# Carte_EV_2018.net
KiCad netlist of a schematic drawn in Altium Designer
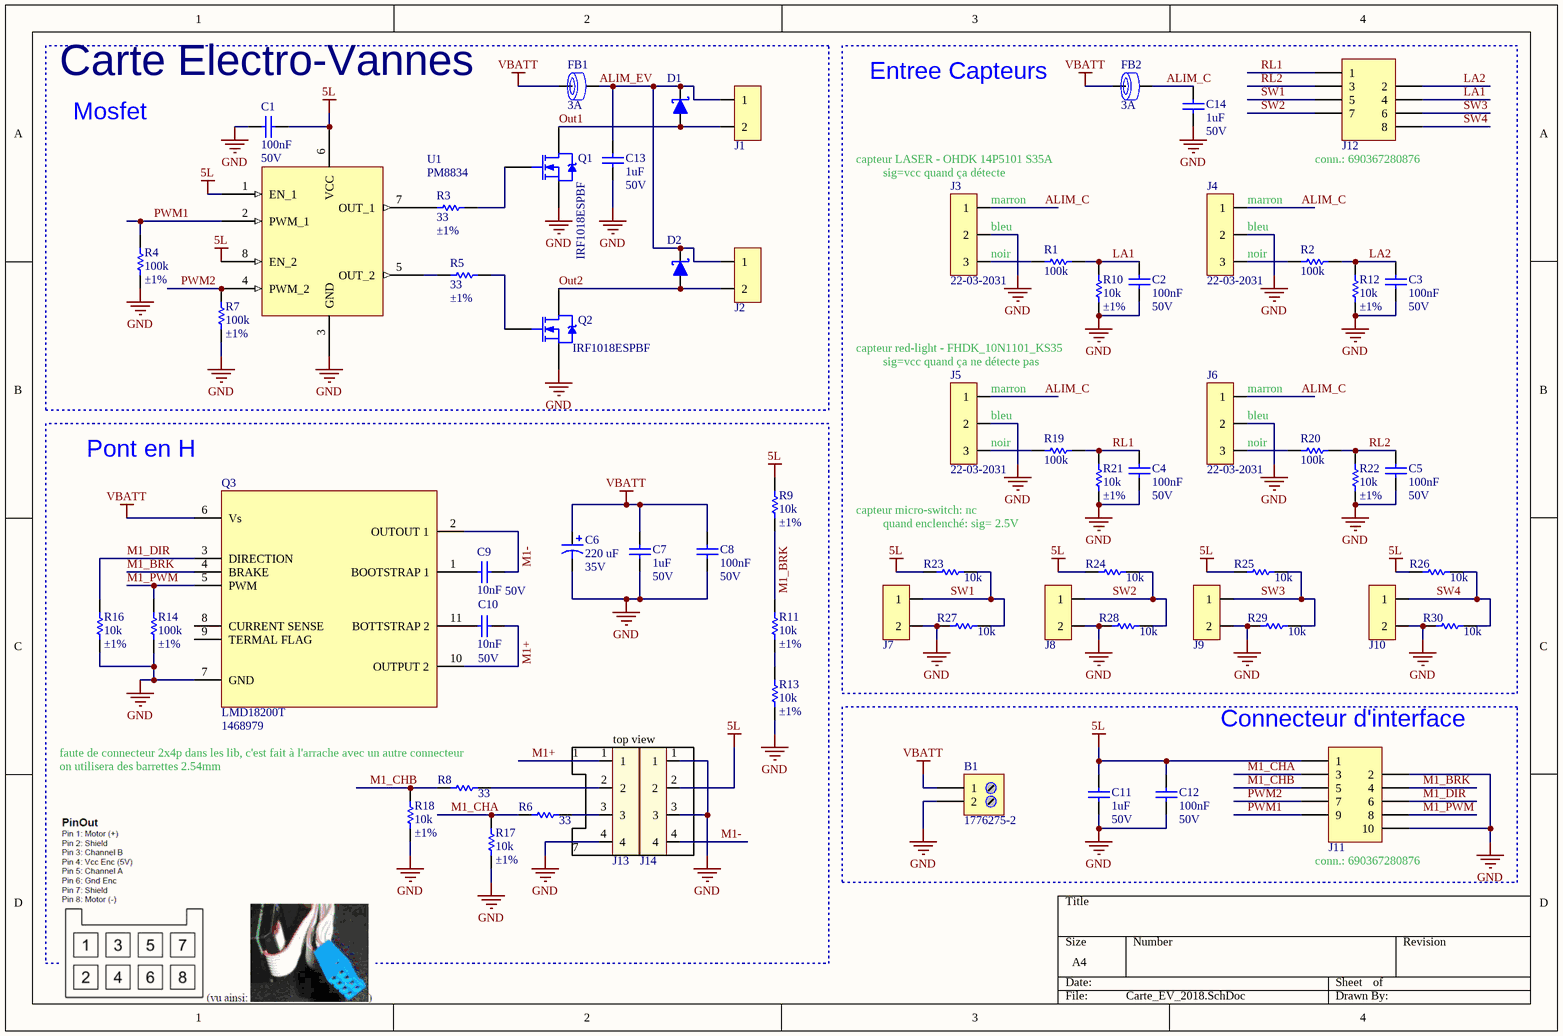
[diagram p0: Carte_EV_2018.SchDoc]

(export (version "E")
  (design (tool "Eeschema 10.0.6"))
  (components
    (comp (ref "B1")
      (value "1776275-2")
      (footprint "BORNIER_2V_3.5MM")
      (description "TERM BLOCK 2POS SIDE ENT 3.5MM")
      (fields (field (name "MANUFACTURER") "TE Connectivity AMP Connectors"))
      (libsource (lib "Divers") (part "1776275-2"))
    )
    (comp (ref "C1")
      (value "100nF")
      (footprint "WCAP-CSGP_0603, 1.6x0.8x0.8")
      (description "CAP CER 100nF 50V X7R 0603")
      (fields
        (field (name "MANUFACTURER") "Wurth Elektronik")
        (field (name "MANUFACTURER PART NUMBER") "885012206095")
        (field (name "RATEDVOLTAGE") "50V")
      )
      (libsource (lib "Condensateur") (part "WCAP-CSGP, 885012206095"))
    )
    (comp (ref "C2")
      (value "100nF")
      (footprint "WCAP-CSGP_0603, 1.6x0.8x0.8")
      (description "CAP CER 100nF 50V X7R 0603")
      (fields
        (field (name "MANUFACTURER") "Wurth Elektronik")
        (field (name "MANUFACTURER PART NUMBER") "885012206095")
        (field (name "RATEDVOLTAGE") "50V")
      )
      (libsource (lib "Condensateur") (part "WCAP-CSGP, 885012206095"))
    )
    (comp (ref "C3")
      (value "100nF")
      (footprint "WCAP-CSGP_0603, 1.6x0.8x0.8")
      (description "CAP CER 100nF 50V X7R 0603")
      (fields
        (field (name "MANUFACTURER") "Wurth Elektronik")
        (field (name "MANUFACTURER PART NUMBER") "885012206095")
        (field (name "RATEDVOLTAGE") "50V")
      )
      (libsource (lib "Condensateur") (part "WCAP-CSGP, 885012206095"))
    )
    (comp (ref "C4")
      (value "100nF")
      (footprint "WCAP-CSGP_0603, 1.6x0.8x0.8")
      (description "CAP CER 100nF 50V X7R 0603")
      (fields
        (field (name "MANUFACTURER") "Wurth Elektronik")
        (field (name "MANUFACTURER PART NUMBER") "885012206095")
        (field (name "RATEDVOLTAGE") "50V")
      )
      (libsource (lib "Condensateur") (part "WCAP-CSGP, 885012206095"))
    )
    (comp (ref "C5")
      (value "100nF")
      (footprint "WCAP-CSGP_0603, 1.6x0.8x0.8")
      (description "CAP CER 100nF 50V X7R 0603")
      (fields
        (field (name "MANUFACTURER") "Wurth Elektronik")
        (field (name "MANUFACTURER PART NUMBER") "885012206095")
        (field (name "RATEDVOLTAGE") "50V")
      )
      (libsource (lib "Condensateur") (part "WCAP-CSGP, 885012206095"))
    )
    (comp (ref "C6")
      (value "220 uF")
      (footprint "WCAP-ATG8_8x11.5x3.5x0.5")
      (description "CAP Alu 220 UF 20% 35 V")
      (fields
        (field (name "MANUFACTURER") "Wurth Elektronik")
        (field (name "MANUFACTURER PART NUMBER") "860010574011")
        (field (name "RATEDVOLTAGE") "35V")
      )
      (libsource (lib "Condensateur") (part "WCAP-ATG8, 860010574011"))
    )
    (comp (ref "C7")
      (value "1uF")
      (footprint "WCAP-CSGP_0805, 2x1.25x1.25")
      (description "CAP CER 1uF 50V X7R 0805")
      (fields
        (field (name "MANUFACTURER") "Wurth Elektronik")
        (field (name "MANUFACTURER PART NUMBER") "885012207103")
        (field (name "RATEDVOLTAGE") "50V")
      )
      (libsource (lib "Condensateur") (part "WCAP-CSGP, 885012207103"))
    )
    (comp (ref "C8")
      (value "100nF")
      (footprint "WCAP-CSGP_0603, 1.6x0.8x0.8")
      (description "CAP CER 100nF 50V X7R 0603")
      (fields
        (field (name "MANUFACTURER") "Wurth Elektronik")
        (field (name "MANUFACTURER PART NUMBER") "885012206095")
        (field (name "RATEDVOLTAGE") "50V")
      )
      (libsource (lib "Condensateur") (part "WCAP-CSGP, 885012206095"))
    )
    (comp (ref "C9")
      (value "10nF")
      (footprint "WCAP-CSGP_0603, 1.6x0.8x0.8")
      (description "CAP CER 10nF 50V X7R 0603")
      (fields
        (field (name "MANUFACTURER") "Wurth Elektronik")
        (field (name "MANUFACTURER PART NUMBER") "885012206089")
        (field (name "RATEDVOLTAGE") "50V")
      )
      (libsource (lib "Condensateur") (part "WCAP-CSGP, 885012206089"))
    )
    (comp (ref "C10")
      (value "10nF")
      (footprint "WCAP-CSGP_0603, 1.6x0.8x0.8")
      (description "CAP CER 10nF 50V X7R 0603")
      (fields
        (field (name "MANUFACTURER") "Wurth Elektronik")
        (field (name "MANUFACTURER PART NUMBER") "885012206089")
        (field (name "RATEDVOLTAGE") "50V")
      )
      (libsource (lib "Condensateur") (part "WCAP-CSGP, 885012206089"))
    )
    (comp (ref "C11")
      (value "1uF")
      (footprint "WCAP-CSGP_0805, 2x1.25x1.25")
      (description "CAP CER 1uF 50V X7R 0805")
      (fields
        (field (name "MANUFACTURER") "Wurth Elektronik")
        (field (name "MANUFACTURER PART NUMBER") "885012207103")
        (field (name "RATEDVOLTAGE") "50V")
      )
      (libsource (lib "Condensateur") (part "WCAP-CSGP, 885012207103"))
    )
    (comp (ref "C12")
      (value "100nF")
      (footprint "WCAP-CSGP_0603, 1.6x0.8x0.8")
      (description "CAP CER 100nF 50V X7R 0603")
      (fields
        (field (name "MANUFACTURER") "Wurth Elektronik")
        (field (name "MANUFACTURER PART NUMBER") "885012206095")
        (field (name "RATEDVOLTAGE") "50V")
      )
      (libsource (lib "Condensateur") (part "WCAP-CSGP, 885012206095"))
    )
    (comp (ref "C13")
      (value "1uF")
      (footprint "WCAP-CSGP_0805, 2x1.25x1.25")
      (description "CAP CER 1uF 50V X7R 0805")
      (fields
        (field (name "MANUFACTURER") "Wurth Elektronik")
        (field (name "MANUFACTURER PART NUMBER") "885012207103")
        (field (name "RATEDVOLTAGE") "50V")
      )
      (libsource (lib "Condensateur") (part "WCAP-CSGP, 885012207103"))
    )
    (comp (ref "C14")
      (value "1uF")
      (footprint "WCAP-CSGP_0805, 2x1.25x1.25")
      (description "CAP CER 1uF 50V X7R 0805")
      (fields
        (field (name "MANUFACTURER") "Wurth Elektronik")
        (field (name "MANUFACTURER PART NUMBER") "885012207103")
        (field (name "RATEDVOLTAGE") "50V")
      )
      (libsource (lib "Condensateur") (part "WCAP-CSGP, 885012207103"))
    )
    (comp (ref "D1")
      (value "RBR3MM40ATFTR")
      (footprint "Diode:SOD-123FL")
      (description "DIODE SCHOTTKY 40V 3A SOD123-FL")
      (fields (field (name "MANUFACTURER") "ROHM"))
      (libsource (lib "Diode") (part "RBR3MM40ATFTR"))
    )
    (comp (ref "D2")
      (value "RBR3MM40ATFTR")
      (footprint "Diode:SOD-123FL")
      (description "DIODE SCHOTTKY 40V 3A SOD123-FL")
      (fields (field (name "MANUFACTURER") "ROHM"))
      (libsource (lib "Diode") (part "RBR3MM40ATFTR"))
    )
    (comp (ref "FB1")
      (value "742792023")
      (footprint "WE-CBF_0805_High Current")
      (description "Ferrite Bead 120ohm 0805 max3.0A")
      (fields (field (name "MANUFACTURER") "Wurth Elektronik") (field (name "RATEDCURRENT") "3A"))
      (libsource (lib "Inductance") (part "WE-CBF, 742792023"))
    )
    (comp (ref "FB2")
      (value "742792023")
      (footprint "WE-CBF_0805_High Current")
      (description "Ferrite Bead 120ohm 0805 max3.0A")
      (fields (field (name "MANUFACTURER") "Wurth Elektronik") (field (name "RATEDCURRENT") "3A"))
      (libsource (lib "Inductance") (part "WE-CBF, 742792023"))
    )
    (comp (ref "J1")
      (value "22-03-2021")
      (footprint "22-03-2021")
      (libsource (lib "Connecteurs") (part "22-03-2021"))
    )
    (comp (ref "J2")
      (value "22-03-2021")
      (footprint "22-03-2021")
      (libsource (lib "Connecteurs") (part "22-03-2021"))
    )
    (comp (ref "J3")
      (value "22-03-2031")
      (footprint "22-03-2031")
      (libsource (lib "Connecteurs") (part "22-03-2031"))
    )
    (comp (ref "J4")
      (value "22-03-2031")
      (footprint "22-03-2031")
      (libsource (lib "Connecteurs") (part "22-03-2031"))
    )
    (comp (ref "J5")
      (value "22-03-2031")
      (footprint "22-03-2031")
      (libsource (lib "Connecteurs") (part "22-03-2031"))
    )
    (comp (ref "J6")
      (value "22-03-2031")
      (footprint "22-03-2031")
      (libsource (lib "Connecteurs") (part "22-03-2031"))
    )
    (comp (ref "J7") (value "22-03-2021") (footprint "22-03-2021") (libsource (lib "") (part "22-03-2021_1")))
    (comp (ref "J8") (value "22-03-2021") (footprint "22-03-2021") (libsource (lib "") (part "22-03-2021_1")))
    (comp (ref "J9") (value "22-03-2021") (footprint "22-03-2021") (libsource (lib "") (part "22-03-2021_1")))
    (comp (ref "J10")
      (value "22-03-2021")
      (footprint "22-03-2021")
      (libsource (lib "") (part "22-03-2021_1"))
    )
    (comp (ref "J11")
      (value "690367281076")
      (footprint "690367281076")
      (description "WR-MM 10p Female SMT Connector with Polarization")
      (fields (field (name "MANUFACTURER") "Wurth Electronics Inc."))
      (libsource (lib "Connecteurs") (part "690367281076"))
    )
    (comp (ref "J12")
      (value "690367280876")
      (footprint "690367280876")
      (description "WR-MM 8p Female SMT Connector with Polarization")
      (fields (field (name "MANUFACTURER") "Wurth Electronics Inc."))
      (libsource (lib "Connecteurs") (part "690367280876"))
    )
    (comp (ref "J13")
      (value "22-27-2041")
      (footprint "22-27-2041")
      (fields (field (name "MANUFACTURER PART NUMBER") "22-27-2041.."))
      (libsource (lib "") (part "22-27-2041_1"))
    )
    (comp (ref "J14")
      (value "22-27-2041")
      (footprint "22-27-2041")
      (fields (field (name "MANUFACTURER PART NUMBER") "22-27-2041.."))
      (libsource (lib "Connecteurs") (part "22-27-2041"))
    )
    (comp (ref "Q1")
      (value "IRF1018ESPBF")
      (footprint "D2Pak / AAVID 7109DG")
      (description "MOSFET N-CH 60V 79A D2PAK")
      (fields (field (name "MANUFACTURER") "Infineon Technologies"))
      (libsource (lib "Transistors") (part "IRF1018ESPBF"))
    )
    (comp (ref "Q2")
      (value "IRF1018ESPBF")
      (footprint "D2Pak / AAVID 7109DG")
      (description "MOSFET N-CH 60V 79A D2PAK")
      (fields (field (name "MANUFACTURER") "Infineon Technologies"))
      (libsource (lib "Transistors") (part "IRF1018ESPBF"))
    )
    (comp (ref "Q3")
      (value "LMD18200T")
      (footprint "LMD18200T")
      (fields
        (field (name "MANUFACTURER PART NUMBER") "LMD18200T/NOPB")
        (field (name "MANUFACTURER") "TEXAS INSTRUMENTS")
        (field (name "SUPPLIER PART NUMBER 1") "1468979")
      )
      (libsource (lib "Transistors") (part "LMD18200T"))
    )
    (comp (ref "R1")
      (value "100k")
      (footprint "RESC1608X06N")
      (description "RES SMD 100K OHM 1% 1/10W 0603")
      (fields
        (field (name "MANUFACTURER") "Yageo")
        (field (name "MANUFACTURER PART NUMBER") "RC0603FR-07100KL")
      )
      (libsource (lib "Resistance") (part "RC0603FR-07100KL"))
    )
    (comp (ref "R2")
      (value "100k")
      (footprint "RESC1608X06N")
      (description "RES SMD 100K OHM 1% 1/10W 0603")
      (fields
        (field (name "MANUFACTURER") "Yageo")
        (field (name "MANUFACTURER PART NUMBER") "RC0603FR-07100KL")
      )
      (libsource (lib "Resistance") (part "RC0603FR-07100KL"))
    )
    (comp (ref "R3")
      (value "33")
      (footprint "RESC1608X06N")
      (description "RES SMD 33 OHM 1% 1/10W 0603")
      (fields
        (field (name "MANUFACTURER") "Yageo")
        (field (name "MANUFACTURER PART NUMBER") "RC0603FR-0733RL")
        (field (name "PRECISION") "±1%")
      )
      (libsource (lib "Resistance") (part "RC0603FR-0733RL"))
    )
    (comp (ref "R4")
      (value "100k")
      (footprint "RESC1608X06N")
      (description "RES SMD 100K OHM 1% 1/10W 0603")
      (fields
        (field (name "MANUFACTURER") "Yageo")
        (field (name "MANUFACTURER PART NUMBER") "RC0603FR-07100KL")
        (field (name "PRECISION") "±1%")
      )
      (libsource (lib "Resistance") (part "RC0603FR-07100KL"))
    )
    (comp (ref "R5")
      (value "33")
      (footprint "RESC1608X06N")
      (description "RES SMD 33 OHM 1% 1/10W 0603")
      (fields
        (field (name "MANUFACTURER") "Yageo")
        (field (name "MANUFACTURER PART NUMBER") "RC0603FR-0733RL")
        (field (name "PRECISION") "±1%")
      )
      (libsource (lib "Resistance") (part "RC0603FR-0733RL"))
    )
    (comp (ref "R6")
      (value "33")
      (footprint "RESC1608X06N")
      (description "RES SMD 33 OHM 1% 1/10W 0603")
      (fields
        (field (name "MANUFACTURER") "Yageo")
        (field (name "MANUFACTURER PART NUMBER") "RC0603FR-0733RL")
      )
      (libsource (lib "Resistance") (part "RC0603FR-0733RL"))
    )
    (comp (ref "R7")
      (value "100k")
      (footprint "RESC1608X06N")
      (description "RES SMD 100K OHM 1% 1/10W 0603")
      (fields
        (field (name "MANUFACTURER") "Yageo")
        (field (name "MANUFACTURER PART NUMBER") "RC0603FR-07100KL")
        (field (name "PRECISION") "±1%")
      )
      (libsource (lib "Resistance") (part "RC0603FR-07100KL"))
    )
    (comp (ref "R8")
      (value "33")
      (footprint "RESC1608X06N")
      (description "RES SMD 33 OHM 1% 1/10W 0603")
      (fields
        (field (name "MANUFACTURER") "Yageo")
        (field (name "MANUFACTURER PART NUMBER") "RC0603FR-0733RL")
      )
      (libsource (lib "Resistance") (part "RC0603FR-0733RL"))
    )
    (comp (ref "R9")
      (value "10k")
      (footprint "RESC1608X06N")
      (description "RES SMD 10K OHM 1% 1/10W 0603")
      (fields
        (field (name "MANUFACTURER") "Yageo")
        (field (name "MANUFACTURER PART NUMBER") "RC0603FR-0710KL")
        (field (name "PRECISION") "±1%")
      )
      (libsource (lib "Resistance") (part "RC0603FR-0710KL"))
    )
    (comp (ref "R10")
      (value "10k")
      (footprint "RESC1608X06N")
      (description "RES SMD 10K OHM 1% 1/10W 0603")
      (fields
        (field (name "MANUFACTURER") "Yageo")
        (field (name "MANUFACTURER PART NUMBER") "RC0603FR-0710KL")
        (field (name "PRECISION") "±1%")
      )
      (libsource (lib "Resistance") (part "RC0603FR-0710KL"))
    )
    (comp (ref "R11")
      (value "10k")
      (footprint "RESC1608X06N")
      (description "RES SMD 10K OHM 1% 1/10W 0603")
      (fields
        (field (name "MANUFACTURER") "Yageo")
        (field (name "MANUFACTURER PART NUMBER") "RC0603FR-0710KL")
        (field (name "PRECISION") "±1%")
      )
      (libsource (lib "Resistance") (part "RC0603FR-0710KL"))
    )
    (comp (ref "R12")
      (value "10k")
      (footprint "RESC1608X06N")
      (description "RES SMD 10K OHM 1% 1/10W 0603")
      (fields
        (field (name "MANUFACTURER") "Yageo")
        (field (name "MANUFACTURER PART NUMBER") "RC0603FR-0710KL")
        (field (name "PRECISION") "±1%")
      )
      (libsource (lib "Resistance") (part "RC0603FR-0710KL"))
    )
    (comp (ref "R13")
      (value "10k")
      (footprint "RESC1608X06N")
      (description "RES SMD 10K OHM 1% 1/10W 0603")
      (fields
        (field (name "MANUFACTURER") "Yageo")
        (field (name "MANUFACTURER PART NUMBER") "RC0603FR-0710KL")
        (field (name "PRECISION") "±1%")
      )
      (libsource (lib "Resistance") (part "RC0603FR-0710KL"))
    )
    (comp (ref "R14")
      (value "100k")
      (footprint "RESC1608X06N")
      (description "RES SMD 100K OHM 1% 1/10W 0603")
      (fields
        (field (name "MANUFACTURER") "Yageo")
        (field (name "MANUFACTURER PART NUMBER") "RC0603FR-07100KL")
        (field (name "PRECISION") "±1%")
      )
      (libsource (lib "Resistance") (part "RC0603FR-07100KL"))
    )
    (comp (ref "R16")
      (value "10k")
      (footprint "RESC1608X06N")
      (description "RES SMD 10K OHM 1% 1/10W 0603")
      (fields
        (field (name "MANUFACTURER") "Yageo")
        (field (name "MANUFACTURER PART NUMBER") "RC0603FR-0710KL")
        (field (name "PRECISION") "±1%")
      )
      (libsource (lib "Resistance") (part "RC0603FR-0710KL"))
    )
    (comp (ref "R17")
      (value "10k")
      (footprint "RESC1608X06N")
      (description "RES SMD 10K OHM 1% 1/10W 0603")
      (fields
        (field (name "MANUFACTURER") "Yageo")
        (field (name "MANUFACTURER PART NUMBER") "RC0603FR-0710KL")
        (field (name "PRECISION") "±1%")
      )
      (libsource (lib "Resistance") (part "RC0603FR-0710KL"))
    )
    (comp (ref "R18")
      (value "10k")
      (footprint "RESC1608X06N")
      (description "RES SMD 10K OHM 1% 1/10W 0603")
      (fields
        (field (name "MANUFACTURER") "Yageo")
        (field (name "MANUFACTURER PART NUMBER") "RC0603FR-0710KL")
        (field (name "PRECISION") "±1%")
      )
      (libsource (lib "Resistance") (part "RC0603FR-0710KL"))
    )
    (comp (ref "R19")
      (value "100k")
      (footprint "RESC1608X06N")
      (description "RES SMD 100K OHM 1% 1/10W 0603")
      (fields
        (field (name "MANUFACTURER") "Yageo")
        (field (name "MANUFACTURER PART NUMBER") "RC0603FR-07100KL")
      )
      (libsource (lib "Resistance") (part "RC0603FR-07100KL"))
    )
    (comp (ref "R20")
      (value "100k")
      (footprint "RESC1608X06N")
      (description "RES SMD 100K OHM 1% 1/10W 0603")
      (fields
        (field (name "MANUFACTURER") "Yageo")
        (field (name "MANUFACTURER PART NUMBER") "RC0603FR-07100KL")
      )
      (libsource (lib "Resistance") (part "RC0603FR-07100KL"))
    )
    (comp (ref "R21")
      (value "10k")
      (footprint "RESC1608X06N")
      (description "RES SMD 10K OHM 1% 1/10W 0603")
      (fields
        (field (name "MANUFACTURER") "Yageo")
        (field (name "MANUFACTURER PART NUMBER") "RC0603FR-0710KL")
        (field (name "PRECISION") "±1%")
      )
      (libsource (lib "Resistance") (part "RC0603FR-0710KL"))
    )
    (comp (ref "R22")
      (value "10k")
      (footprint "RESC1608X06N")
      (description "RES SMD 10K OHM 1% 1/10W 0603")
      (fields
        (field (name "MANUFACTURER") "Yageo")
        (field (name "MANUFACTURER PART NUMBER") "RC0603FR-0710KL")
        (field (name "PRECISION") "±1%")
      )
      (libsource (lib "Resistance") (part "RC0603FR-0710KL"))
    )
    (comp (ref "R23")
      (value "10k")
      (footprint "RESC1608X06N")
      (description "RES SMD 10K OHM 1% 1/10W 0603")
      (fields
        (field (name "MANUFACTURER") "Yageo")
        (field (name "MANUFACTURER PART NUMBER") "RC0603FR-0710KL")
      )
      (libsource (lib "Resistance") (part "RC0603FR-0710KL"))
    )
    (comp (ref "R24")
      (value "10k")
      (footprint "RESC1608X06N")
      (description "RES SMD 10K OHM 1% 1/10W 0603")
      (fields
        (field (name "MANUFACTURER") "Yageo")
        (field (name "MANUFACTURER PART NUMBER") "RC0603FR-0710KL")
      )
      (libsource (lib "Resistance") (part "RC0603FR-0710KL"))
    )
    (comp (ref "R25")
      (value "10k")
      (footprint "RESC1608X06N")
      (description "RES SMD 10K OHM 1% 1/10W 0603")
      (fields
        (field (name "MANUFACTURER") "Yageo")
        (field (name "MANUFACTURER PART NUMBER") "RC0603FR-0710KL")
      )
      (libsource (lib "Resistance") (part "RC0603FR-0710KL"))
    )
    (comp (ref "R26")
      (value "10k")
      (footprint "RESC1608X06N")
      (description "RES SMD 10K OHM 1% 1/10W 0603")
      (fields
        (field (name "MANUFACTURER") "Yageo")
        (field (name "MANUFACTURER PART NUMBER") "RC0603FR-0710KL")
      )
      (libsource (lib "Resistance") (part "RC0603FR-0710KL"))
    )
    (comp (ref "R27")
      (value "10k")
      (footprint "RESC1608X06N")
      (description "RES SMD 10K OHM 1% 1/10W 0603")
      (fields
        (field (name "MANUFACTURER") "Yageo")
        (field (name "MANUFACTURER PART NUMBER") "RC0603FR-0710KL")
      )
      (libsource (lib "Resistance") (part "RC0603FR-0710KL"))
    )
    (comp (ref "R28")
      (value "10k")
      (footprint "RESC1608X06N")
      (description "RES SMD 10K OHM 1% 1/10W 0603")
      (fields
        (field (name "MANUFACTURER") "Yageo")
        (field (name "MANUFACTURER PART NUMBER") "RC0603FR-0710KL")
      )
      (libsource (lib "Resistance") (part "RC0603FR-0710KL"))
    )
    (comp (ref "R29")
      (value "10k")
      (footprint "RESC1608X06N")
      (description "RES SMD 10K OHM 1% 1/10W 0603")
      (fields
        (field (name "MANUFACTURER") "Yageo")
        (field (name "MANUFACTURER PART NUMBER") "RC0603FR-0710KL")
      )
      (libsource (lib "Resistance") (part "RC0603FR-0710KL"))
    )
    (comp (ref "R30")
      (value "10k")
      (footprint "RESC1608X06N")
      (description "RES SMD 10K OHM 1% 1/10W 0603")
      (fields
        (field (name "MANUFACTURER") "Yageo")
        (field (name "MANUFACTURER PART NUMBER") "RC0603FR-0710KL")
      )
      (libsource (lib "Resistance") (part "RC0603FR-0710KL"))
    )
    (comp (ref "U1")
      (value "PM8834")
      (footprint "SOIC127P600X175-8N")
      (description "IC MOSFET DVR 4A DUAL 8SOIC")
      (fields (field (name "MANUFACTURER") "STMicroelectronics"))
      (libsource (lib "CI") (part "PM8834"))
    )
  )
  (nets
    (net (code "1") (name "/ALIM_C") (class "Default")
      (node (ref "C14") (pin "2") (pinfunction "2_2") (pintype "passive"))
      (node (ref "FB2") (pin "2") (pinfunction "2_2") (pintype "passive"))
      (node (ref "J3") (pin "1") (pinfunction "1_1") (pintype "passive"))
      (node (ref "J4") (pin "1") (pinfunction "1_1") (pintype "passive"))
      (node (ref "J5") (pin "1") (pinfunction "1_1") (pintype "passive"))
      (node (ref "J6") (pin "1") (pinfunction "1_1") (pintype "passive"))
    )
    (net (code "2") (name "/ALIM_EV") (class "Default")
      (node (ref "C13") (pin "2") (pinfunction "2_2") (pintype "passive"))
      (node (ref "D1") (pin "2") (pintype "passive"))
      (node (ref "D2") (pin "2") (pintype "passive"))
      (node (ref "FB1") (pin "2") (pinfunction "2_2") (pintype "passive"))
      (node (ref "J1") (pin "1") (pinfunction "1_1") (pintype "passive"))
      (node (ref "J2") (pin "1") (pinfunction "1_1") (pintype "passive"))
    )
    (net (code "3") (name "/LA1") (class "Default")
      (node (ref "C2") (pin "2") (pinfunction "2_2") (pintype "passive"))
      (node (ref "J12") (pin "4") (pinfunction "4_4") (pintype "passive"))
      (node (ref "R1") (pin "1") (pinfunction "1_1") (pintype "passive"))
      (node (ref "R10") (pin "2") (pinfunction "2_2") (pintype "passive"))
    )
    (net (code "4") (name "/LA2") (class "Default")
      (node (ref "C3") (pin "2") (pinfunction "2_2") (pintype "passive"))
      (node (ref "J12") (pin "2") (pinfunction "2_2") (pintype "passive"))
      (node (ref "R12") (pin "2") (pinfunction "2_2") (pintype "passive"))
      (node (ref "R2") (pin "1") (pinfunction "1_1") (pintype "passive"))
    )
    (net (code "5") (name "/M1+") (class "Default")
      (node (ref "C10") (pin "2") (pinfunction "2_2") (pintype "passive"))
      (node (ref "J13") (pin "1") (pinfunction "1_1") (pintype "passive"))
      (node (ref "Q3") (pin "10") (pinfunction "OUTPUT_2_10") (pintype "passive"))
    )
    (net (code "6") (name "/M1-") (class "Default")
      (node (ref "C9") (pin "2") (pinfunction "2_2") (pintype "passive"))
      (node (ref "J14") (pin "4") (pinfunction "4_4") (pintype "power_in"))
      (node (ref "Q3") (pin "2") (pinfunction "OUTOUT_1_2") (pintype "passive"))
    )
    (net (code "7") (name "/M1_BRK") (class "Default")
      (node (ref "J11") (pin "4") (pinfunction "4_4") (pintype "passive"))
      (node (ref "Q3") (pin "4") (pinfunction "BRAKE_4") (pintype "passive"))
      (node (ref "R11") (pin "2") (pinfunction "2_2") (pintype "passive"))
      (node (ref "R9") (pin "1") (pinfunction "1_1") (pintype "passive"))
    )
    (net (code "8") (name "/M1_CHA") (class "Default")
      (node (ref "J11") (pin "3") (pinfunction "3_3") (pintype "passive"))
      (node (ref "R17") (pin "2") (pinfunction "2_2") (pintype "passive"))
      (node (ref "R6") (pin "1") (pinfunction "1_1") (pintype "passive"))
    )
    (net (code "9") (name "/M1_CHB") (class "Default")
      (node (ref "J11") (pin "5") (pinfunction "5_5") (pintype "passive"))
      (node (ref "R18") (pin "2") (pinfunction "2_2") (pintype "passive"))
      (node (ref "R8") (pin "1") (pinfunction "1_1") (pintype "passive"))
    )
    (net (code "10") (name "/M1_DIR") (class "Default")
      (node (ref "J11") (pin "6") (pinfunction "6_6") (pintype "passive"))
      (node (ref "Q3") (pin "3") (pinfunction "DIRECTION_3") (pintype "passive"))
      (node (ref "R16") (pin "2") (pinfunction "2_2") (pintype "passive"))
    )
    (net (code "11") (name "/M1_PWM") (class "Default")
      (node (ref "J11") (pin "8") (pinfunction "8_8") (pintype "passive"))
      (node (ref "Q3") (pin "5") (pinfunction "PWM_5") (pintype "passive"))
      (node (ref "R14") (pin "2") (pinfunction "2_2") (pintype "passive"))
    )
    (net (code "12") (name "/Out1") (class "Default")
      (node (ref "D1") (pin "1") (pintype "passive"))
      (node (ref "J1") (pin "2") (pinfunction "2_2") (pintype "passive"))
      (node (ref "Q1") (pin "2") (pinfunction "D_2") (pintype "passive"))
    )
    (net (code "13") (name "/Out2") (class "Default")
      (node (ref "D2") (pin "1") (pintype "passive"))
      (node (ref "J2") (pin "2") (pinfunction "2_2") (pintype "passive"))
      (node (ref "Q2") (pin "2") (pinfunction "D_2") (pintype "passive"))
    )
    (net (code "14") (name "/PWM1") (class "Default")
      (node (ref "J11") (pin "9") (pinfunction "9_9") (pintype "passive"))
      (node (ref "R4") (pin "2") (pinfunction "2_2") (pintype "passive"))
      (node (ref "U1") (pin "2") (pinfunction "PWM_1_2") (pintype "input"))
    )
    (net (code "15") (name "/PWM2") (class "Default")
      (node (ref "J11") (pin "7") (pinfunction "7_7") (pintype "passive"))
      (node (ref "R7") (pin "2") (pinfunction "2_2") (pintype "passive"))
      (node (ref "U1") (pin "4") (pinfunction "PWM_2_4") (pintype "input"))
    )
    (net (code "16") (name "/RL1") (class "Default")
      (node (ref "C4") (pin "2") (pinfunction "2_2") (pintype "passive"))
      (node (ref "J12") (pin "1") (pinfunction "1_1") (pintype "passive"))
      (node (ref "R19") (pin "1") (pinfunction "1_1") (pintype "passive"))
      (node (ref "R21") (pin "2") (pinfunction "2_2") (pintype "passive"))
    )
    (net (code "17") (name "/RL2") (class "Default")
      (node (ref "C5") (pin "2") (pinfunction "2_2") (pintype "passive"))
      (node (ref "J12") (pin "3") (pinfunction "3_3") (pintype "passive"))
      (node (ref "R20") (pin "1") (pinfunction "1_1") (pintype "passive"))
      (node (ref "R22") (pin "2") (pinfunction "2_2") (pintype "passive"))
    )
    (net (code "18") (name "/SW1") (class "Default")
      (node (ref "J12") (pin "5") (pinfunction "5_5") (pintype "passive"))
      (node (ref "J7") (pin "1") (pinfunction "1_1") (pintype "passive"))
      (node (ref "R23") (pin "1") (pinfunction "1_1") (pintype "passive"))
      (node (ref "R27") (pin "1") (pinfunction "1_1") (pintype "passive"))
    )
    (net (code "19") (name "/SW2") (class "Default")
      (node (ref "J12") (pin "7") (pinfunction "7_7") (pintype "passive"))
      (node (ref "J8") (pin "1") (pinfunction "1_1") (pintype "passive"))
      (node (ref "R24") (pin "1") (pinfunction "1_1") (pintype "passive"))
      (node (ref "R28") (pin "1") (pinfunction "1_1") (pintype "passive"))
    )
    (net (code "20") (name "/SW3") (class "Default")
      (node (ref "J12") (pin "6") (pinfunction "6_6") (pintype "passive"))
      (node (ref "J9") (pin "1") (pinfunction "1_1") (pintype "passive"))
      (node (ref "R25") (pin "1") (pinfunction "1_1") (pintype "passive"))
      (node (ref "R29") (pin "1") (pinfunction "1_1") (pintype "passive"))
    )
    (net (code "21") (name "/SW4") (class "Default")
      (node (ref "J10") (pin "1") (pinfunction "1_1") (pintype "passive"))
      (node (ref "J12") (pin "8") (pinfunction "8_8") (pintype "passive"))
      (node (ref "R26") (pin "1") (pinfunction "1_1") (pintype "passive"))
      (node (ref "R30") (pin "1") (pinfunction "1_1") (pintype "passive"))
    )
    (net (code "22") (name "5L") (class "Default")
      (node (ref "C1") (pin "2") (pinfunction "2_2") (pintype "passive"))
      (node (ref "C11") (pin "2") (pinfunction "2_2") (pintype "passive"))
      (node (ref "C12") (pin "2") (pinfunction "2_2") (pintype "passive"))
      (node (ref "J11") (pin "1") (pinfunction "1_1") (pintype "passive"))
      (node (ref "J14") (pin "2") (pinfunction "2_2") (pintype "passive"))
      (node (ref "R23") (pin "2") (pinfunction "2_2") (pintype "passive"))
      (node (ref "R24") (pin "2") (pinfunction "2_2") (pintype "passive"))
      (node (ref "R25") (pin "2") (pinfunction "2_2") (pintype "passive"))
      (node (ref "R26") (pin "2") (pinfunction "2_2") (pintype "passive"))
      (node (ref "R9") (pin "2") (pinfunction "2_2") (pintype "passive"))
      (node (ref "U1") (pin "1") (pinfunction "EN_1_1") (pintype "input"))
      (node (ref "U1") (pin "6") (pinfunction "VCC_6") (pintype "power_in"))
      (node (ref "U1") (pin "8") (pinfunction "EN_2_8") (pintype "input"))
    )
    (net (code "23") (name "GND") (class "Default")
      (node (ref "B1") (pin "2") (pinfunction "2_2") (pintype "passive"))
      (node (ref "C1") (pin "1") (pinfunction "1_1") (pintype "passive"))
      (node (ref "C11") (pin "1") (pinfunction "1_1") (pintype "passive"))
      (node (ref "C12") (pin "1") (pinfunction "1_1") (pintype "passive"))
      (node (ref "C13") (pin "1") (pinfunction "1_1") (pintype "passive"))
      (node (ref "C14") (pin "1") (pinfunction "1_1") (pintype "passive"))
      (node (ref "C2") (pin "1") (pinfunction "1_1") (pintype "passive"))
      (node (ref "C3") (pin "1") (pinfunction "1_1") (pintype "passive"))
      (node (ref "C4") (pin "1") (pinfunction "1_1") (pintype "passive"))
      (node (ref "C5") (pin "1") (pinfunction "1_1") (pintype "passive"))
      (node (ref "C6") (pin "2") (pinfunction "2_2") (pintype "passive"))
      (node (ref "C7") (pin "1") (pinfunction "1_1") (pintype "passive"))
      (node (ref "C8") (pin "1") (pinfunction "1_1") (pintype "passive"))
      (node (ref "J10") (pin "2") (pinfunction "2_2") (pintype "passive"))
      (node (ref "J11") (pin "10") (pinfunction "10_10") (pintype "passive"))
      (node (ref "J11") (pin "2") (pinfunction "2_2") (pintype "passive"))
      (node (ref "J13") (pin "4") (pinfunction "4_4") (pintype "power_in"))
      (node (ref "J14") (pin "1") (pinfunction "1_1") (pintype "passive"))
      (node (ref "J14") (pin "3") (pinfunction "3_3") (pintype "passive"))
      (node (ref "J3") (pin "2") (pinfunction "2_2") (pintype "passive"))
      (node (ref "J4") (pin "2") (pinfunction "2_2") (pintype "passive"))
      (node (ref "J5") (pin "2") (pinfunction "2_2") (pintype "passive"))
      (node (ref "J6") (pin "2") (pinfunction "2_2") (pintype "passive"))
      (node (ref "J7") (pin "2") (pinfunction "2_2") (pintype "passive"))
      (node (ref "J8") (pin "2") (pinfunction "2_2") (pintype "passive"))
      (node (ref "J9") (pin "2") (pinfunction "2_2") (pintype "passive"))
      (node (ref "Q1") (pin "3") (pinfunction "S_3") (pintype "passive"))
      (node (ref "Q2") (pin "3") (pinfunction "S_3") (pintype "passive"))
      (node (ref "Q3") (pin "7") (pinfunction "GND_7") (pintype "passive"))
      (node (ref "R10") (pin "1") (pinfunction "1_1") (pintype "passive"))
      (node (ref "R12") (pin "1") (pinfunction "1_1") (pintype "passive"))
      (node (ref "R13") (pin "1") (pinfunction "1_1") (pintype "passive"))
      (node (ref "R14") (pin "1") (pinfunction "1_1") (pintype "passive"))
      (node (ref "R16") (pin "1") (pinfunction "1_1") (pintype "passive"))
      (node (ref "R17") (pin "1") (pinfunction "1_1") (pintype "passive"))
      (node (ref "R18") (pin "1") (pinfunction "1_1") (pintype "passive"))
      (node (ref "R21") (pin "1") (pinfunction "1_1") (pintype "passive"))
      (node (ref "R22") (pin "1") (pinfunction "1_1") (pintype "passive"))
      (node (ref "R27") (pin "2") (pinfunction "2_2") (pintype "passive"))
      (node (ref "R28") (pin "2") (pinfunction "2_2") (pintype "passive"))
      (node (ref "R29") (pin "2") (pinfunction "2_2") (pintype "passive"))
      (node (ref "R30") (pin "2") (pinfunction "2_2") (pintype "passive"))
      (node (ref "R4") (pin "1") (pinfunction "1_1") (pintype "passive"))
      (node (ref "R7") (pin "1") (pinfunction "1_1") (pintype "passive"))
      (node (ref "U1") (pin "3") (pinfunction "GND_3") (pintype "power_in"))
    )
    (net (code "24") (name "Net-(J3-Pad3)") (class "Default")
      (node (ref "J3") (pin "3") (pinfunction "3_3") (pintype "passive"))
      (node (ref "R1") (pin "2") (pinfunction "2_2") (pintype "passive"))
    )
    (net (code "25") (name "Net-(J4-Pad3)") (class "Default")
      (node (ref "J4") (pin "3") (pinfunction "3_3") (pintype "passive"))
      (node (ref "R2") (pin "2") (pinfunction "2_2") (pintype "passive"))
    )
    (net (code "26") (name "Net-(J5-Pad3)") (class "Default")
      (node (ref "J5") (pin "3") (pinfunction "3_3") (pintype "passive"))
      (node (ref "R19") (pin "2") (pinfunction "2_2") (pintype "passive"))
    )
    (net (code "27") (name "Net-(J6-Pad3)") (class "Default")
      (node (ref "J6") (pin "3") (pinfunction "3_3") (pintype "passive"))
      (node (ref "R20") (pin "2") (pinfunction "2_2") (pintype "passive"))
    )
    (net (code "28") (name "Net-(J13-Pad2)") (class "Default")
      (node (ref "J13") (pin "2") (pinfunction "2_2") (pintype "passive"))
      (node (ref "R8") (pin "2") (pinfunction "2_2") (pintype "passive"))
    )
    (net (code "29") (name "Net-(J13-Pad3)") (class "Default")
      (node (ref "J13") (pin "3") (pinfunction "3_3") (pintype "passive"))
      (node (ref "R6") (pin "2") (pinfunction "2_2") (pintype "passive"))
    )
    (net (code "30") (name "Net-(Q1-G)") (class "Default")
      (node (ref "Q1") (pin "1") (pinfunction "G_1") (pintype "passive"))
      (node (ref "R3") (pin "2") (pinfunction "2_2") (pintype "passive"))
    )
    (net (code "31") (name "Net-(Q2-G)") (class "Default")
      (node (ref "Q2") (pin "1") (pinfunction "G_1") (pintype "passive"))
      (node (ref "R5") (pin "2") (pinfunction "2_2") (pintype "passive"))
    )
    (net (code "32") (name "Net-(Q3-BOOTSTRAP_1)") (class "Default")
      (node (ref "C9") (pin "1") (pinfunction "1_1") (pintype "passive"))
      (node (ref "Q3") (pin "1") (pinfunction "BOOTSTRAP_1_1") (pintype "passive"))
    )
    (net (code "33") (name "Net-(Q3-BOTTSTRAP_2)") (class "Default")
      (node (ref "C10") (pin "1") (pinfunction "1_1") (pintype "passive"))
      (node (ref "Q3") (pin "11") (pinfunction "BOTTSTRAP_2_11") (pintype "passive"))
    )
    (net (code "34") (name "Net-(R11-Pad1)") (class "Default")
      (node (ref "R11") (pin "1") (pinfunction "1_1") (pintype "passive"))
      (node (ref "R13") (pin "2") (pinfunction "2_2") (pintype "passive"))
    )
    (net (code "35") (name "Net-(U1-OUT_1)") (class "Default")
      (node (ref "R3") (pin "1") (pinfunction "1_1") (pintype "passive"))
      (node (ref "U1") (pin "7") (pinfunction "OUT_1_7") (pintype "output"))
    )
    (net (code "36") (name "Net-(U1-OUT_2)") (class "Default")
      (node (ref "R5") (pin "1") (pinfunction "1_1") (pintype "passive"))
      (node (ref "U1") (pin "5") (pinfunction "OUT_2_5") (pintype "output"))
    )
    (net (code "37") (name "VBATT") (class "Default")
      (node (ref "B1") (pin "1") (pinfunction "1_1") (pintype "passive"))
      (node (ref "C6") (pin "1") (pinfunction "1_1") (pintype "passive"))
      (node (ref "C7") (pin "2") (pinfunction "2_2") (pintype "passive"))
      (node (ref "C8") (pin "2") (pinfunction "2_2") (pintype "passive"))
      (node (ref "FB1") (pin "1") (pinfunction "1_1") (pintype "passive"))
      (node (ref "FB2") (pin "1") (pinfunction "1_1") (pintype "passive"))
      (node (ref "Q3") (pin "6") (pinfunction "Vs_6") (pintype "passive"))
    )
    (net (code "38") (name "unconnected-(Q3-CURRENT_SENSE-Pad8)") (class "Default")
      (node (ref "Q3") (pin "8") (pinfunction "CURRENT_SENSE_8") (pintype "passive"))
    )
    (net (code "39") (name "unconnected-(Q3-TERMAL_FLAG-Pad9)") (class "Default")
      (node (ref "Q3") (pin "9") (pinfunction "TERMAL_FLAG_9") (pintype "passive"))
    )
  )
)
